# TSFF5210.net
KiCad netlist of a schematic drawn in Altium Designer
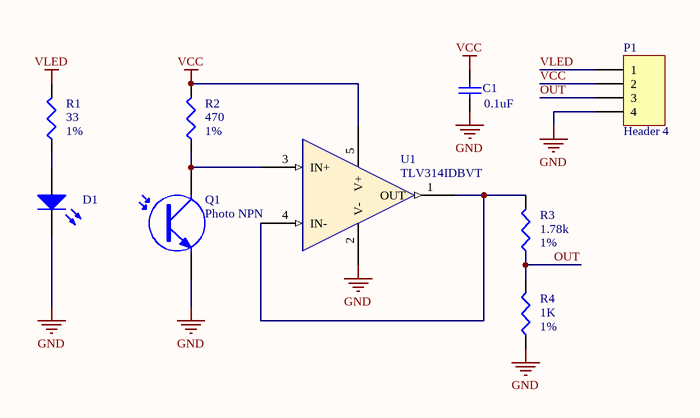
[diagram p0: TSFF5210.SchDoc]

(export (version "E")
  (design (tool "Eeschema 10.0.6"))
  (components
    (comp (ref "C1")
      (value "0.1uF")
      (footprint "J1-0603")
      (description "Capacitor")
      (fields (field (name "Comment") "Cap") (field (name "PUBLISHER") "Altium Limited"))
      (libsource (lib "Miscellaneous Devices") (part "Cap"))
    )
    (comp (ref "D1")
      (value "LED0")
      (footprint "Zhe_Micromouse_Lib:LED-5mm")
      (description "Typical INFRARED GaAs LED")
      (fields (field (name "PUBLISHER") "Altium Limited"))
      (libsource (lib "Miscellaneous Devices") (part "LED0"))
    )
    (comp (ref "P1")
      (value "Header 4")
      (footprint "HDR1X4")
      (description "Header, 4-Pin")
      (fields (field (name "PUBLISHER") "Altium Limited"))
      (libsource (lib "Miscellaneous Connectors") (part "Header 4"))
    )
    (comp (ref "Q1")
      (value "Photo NPN")
      (footprint "LED-5mm")
      (description "NPN Phototransistor")
      (fields (field (name "PUBLISHER") "Altium Limited"))
      (libsource (lib "Zhe_Micromouse_Lib") (part "Photo NPN"))
    )
    (comp (ref "R1")
      (value "33")
      (footprint "1206")
      (description "Resistor")
      (fields
        (field (name "TOLERANCE") "1%")
        (field (name "Comment") "Res3")
        (field (name "PUBLISHER") "Altium Limited")
      )
      (libsource (lib "Miscellaneous Devices") (part "Res3"))
    )
    (comp (ref "R2")
      (value "470")
      (footprint "J1-0603")
      (description "Resistor")
      (fields
        (field (name "TOLERANCE") "1%")
        (field (name "Comment") "Res3")
        (field (name "PUBLISHER") "Altium Limited")
      )
      (libsource (lib "Miscellaneous Devices") (part "Res3"))
    )
    (comp (ref "R3")
      (value "1.78k")
      (footprint "J1-0603")
      (description "Resistor")
      (fields
        (field (name "TOLERANCE") "1%")
        (field (name "Comment") "Res3")
        (field (name "PUBLISHER") "Altium Limited")
      )
      (libsource (lib "Miscellaneous Devices") (part "Res3"))
    )
    (comp (ref "R4")
      (value "1K")
      (footprint "J1-0603")
      (description "Resistor")
      (fields
        (field (name "TOLERANCE") "1%")
        (field (name "Comment") "Res3")
        (field (name "PUBLISHER") "Altium Limited")
      )
      (libsource (lib "Miscellaneous Devices") (part "Res3"))
    )
    (comp (ref "U1")
      (value "TLV314IDBVT")
      (footprint "SOT23-5")
      (libsource (lib "Zhe_Micromouse_Lib") (part "TLV314IDBVT"))
    )
  )
  (nets
    (net (code "1") (name "/OUT") (class "Default")
      (node (ref "P1") (pin "3") (pinfunction "3_3") (pintype "passive"))
      (node (ref "R3") (pin "1") (pinfunction "1_1") (pintype "passive"))
      (node (ref "R4") (pin "2") (pinfunction "2_2") (pintype "passive"))
    )
    (net (code "2") (name "GND") (class "Default")
      (node (ref "C1") (pin "1") (pinfunction "1_1") (pintype "passive"))
      (node (ref "D1") (pin "2") (pinfunction "K_2") (pintype "passive"))
      (node (ref "P1") (pin "4") (pinfunction "4_4") (pintype "passive"))
      (node (ref "Q1") (pin "1") (pinfunction "E_1") (pintype "passive"))
      (node (ref "R4") (pin "1") (pinfunction "1_1") (pintype "passive"))
      (node (ref "U1") (pin "2") (pinfunction "V-_2") (pintype "passive"))
    )
    (net (code "3") (name "Net-(D1-A)") (class "Default")
      (node (ref "D1") (pin "1") (pinfunction "A_1") (pintype "passive"))
      (node (ref "R1") (pin "1") (pinfunction "1_1") (pintype "passive"))
    )
    (net (code "4") (name "Net-(Q1-C)") (class "Default")
      (node (ref "Q1") (pin "2") (pinfunction "C_2") (pintype "passive"))
      (node (ref "R2") (pin "1") (pinfunction "1_1") (pintype "passive"))
      (node (ref "U1") (pin "3") (pinfunction "IN+_3") (pintype "input"))
    )
    (net (code "5") (name "Net-(U1-IN-)") (class "Default")
      (node (ref "R3") (pin "2") (pinfunction "2_2") (pintype "passive"))
      (node (ref "U1") (pin "1") (pinfunction "OUT_1") (pintype "output"))
      (node (ref "U1") (pin "4") (pinfunction "IN-_4") (pintype "input"))
    )
    (net (code "6") (name "VCC") (class "Default")
      (node (ref "C1") (pin "2") (pinfunction "2_2") (pintype "passive"))
      (node (ref "P1") (pin "2") (pinfunction "2_2") (pintype "passive"))
      (node (ref "R2") (pin "2") (pinfunction "2_2") (pintype "passive"))
      (node (ref "U1") (pin "5") (pinfunction "V+_5") (pintype "passive"))
    )
    (net (code "7") (name "VLED") (class "Default")
      (node (ref "P1") (pin "1") (pinfunction "1_1") (pintype "passive"))
      (node (ref "R1") (pin "2") (pinfunction "2_2") (pintype "passive"))
    )
  )
)
